# Sheet7.net
KiCad netlist of a schematic drawn in Altium Designer
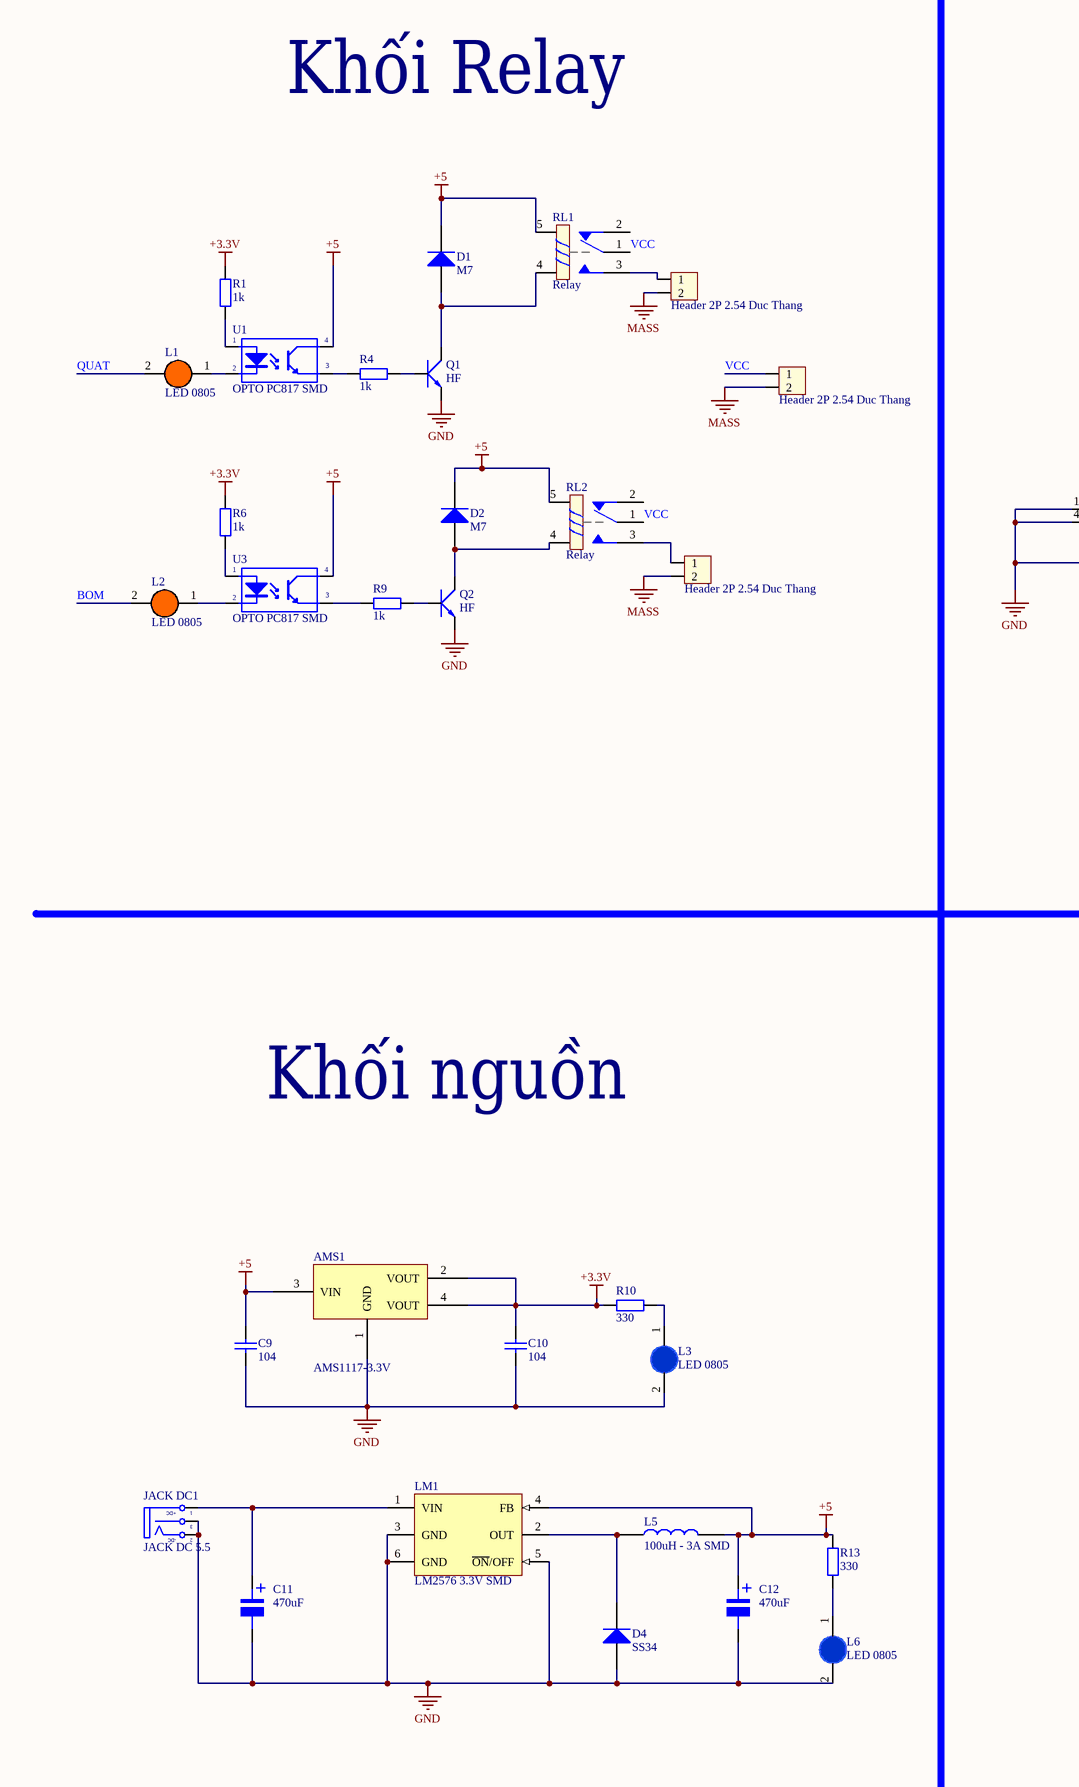
[diagram p0: Sheet7.SchDoc, left]
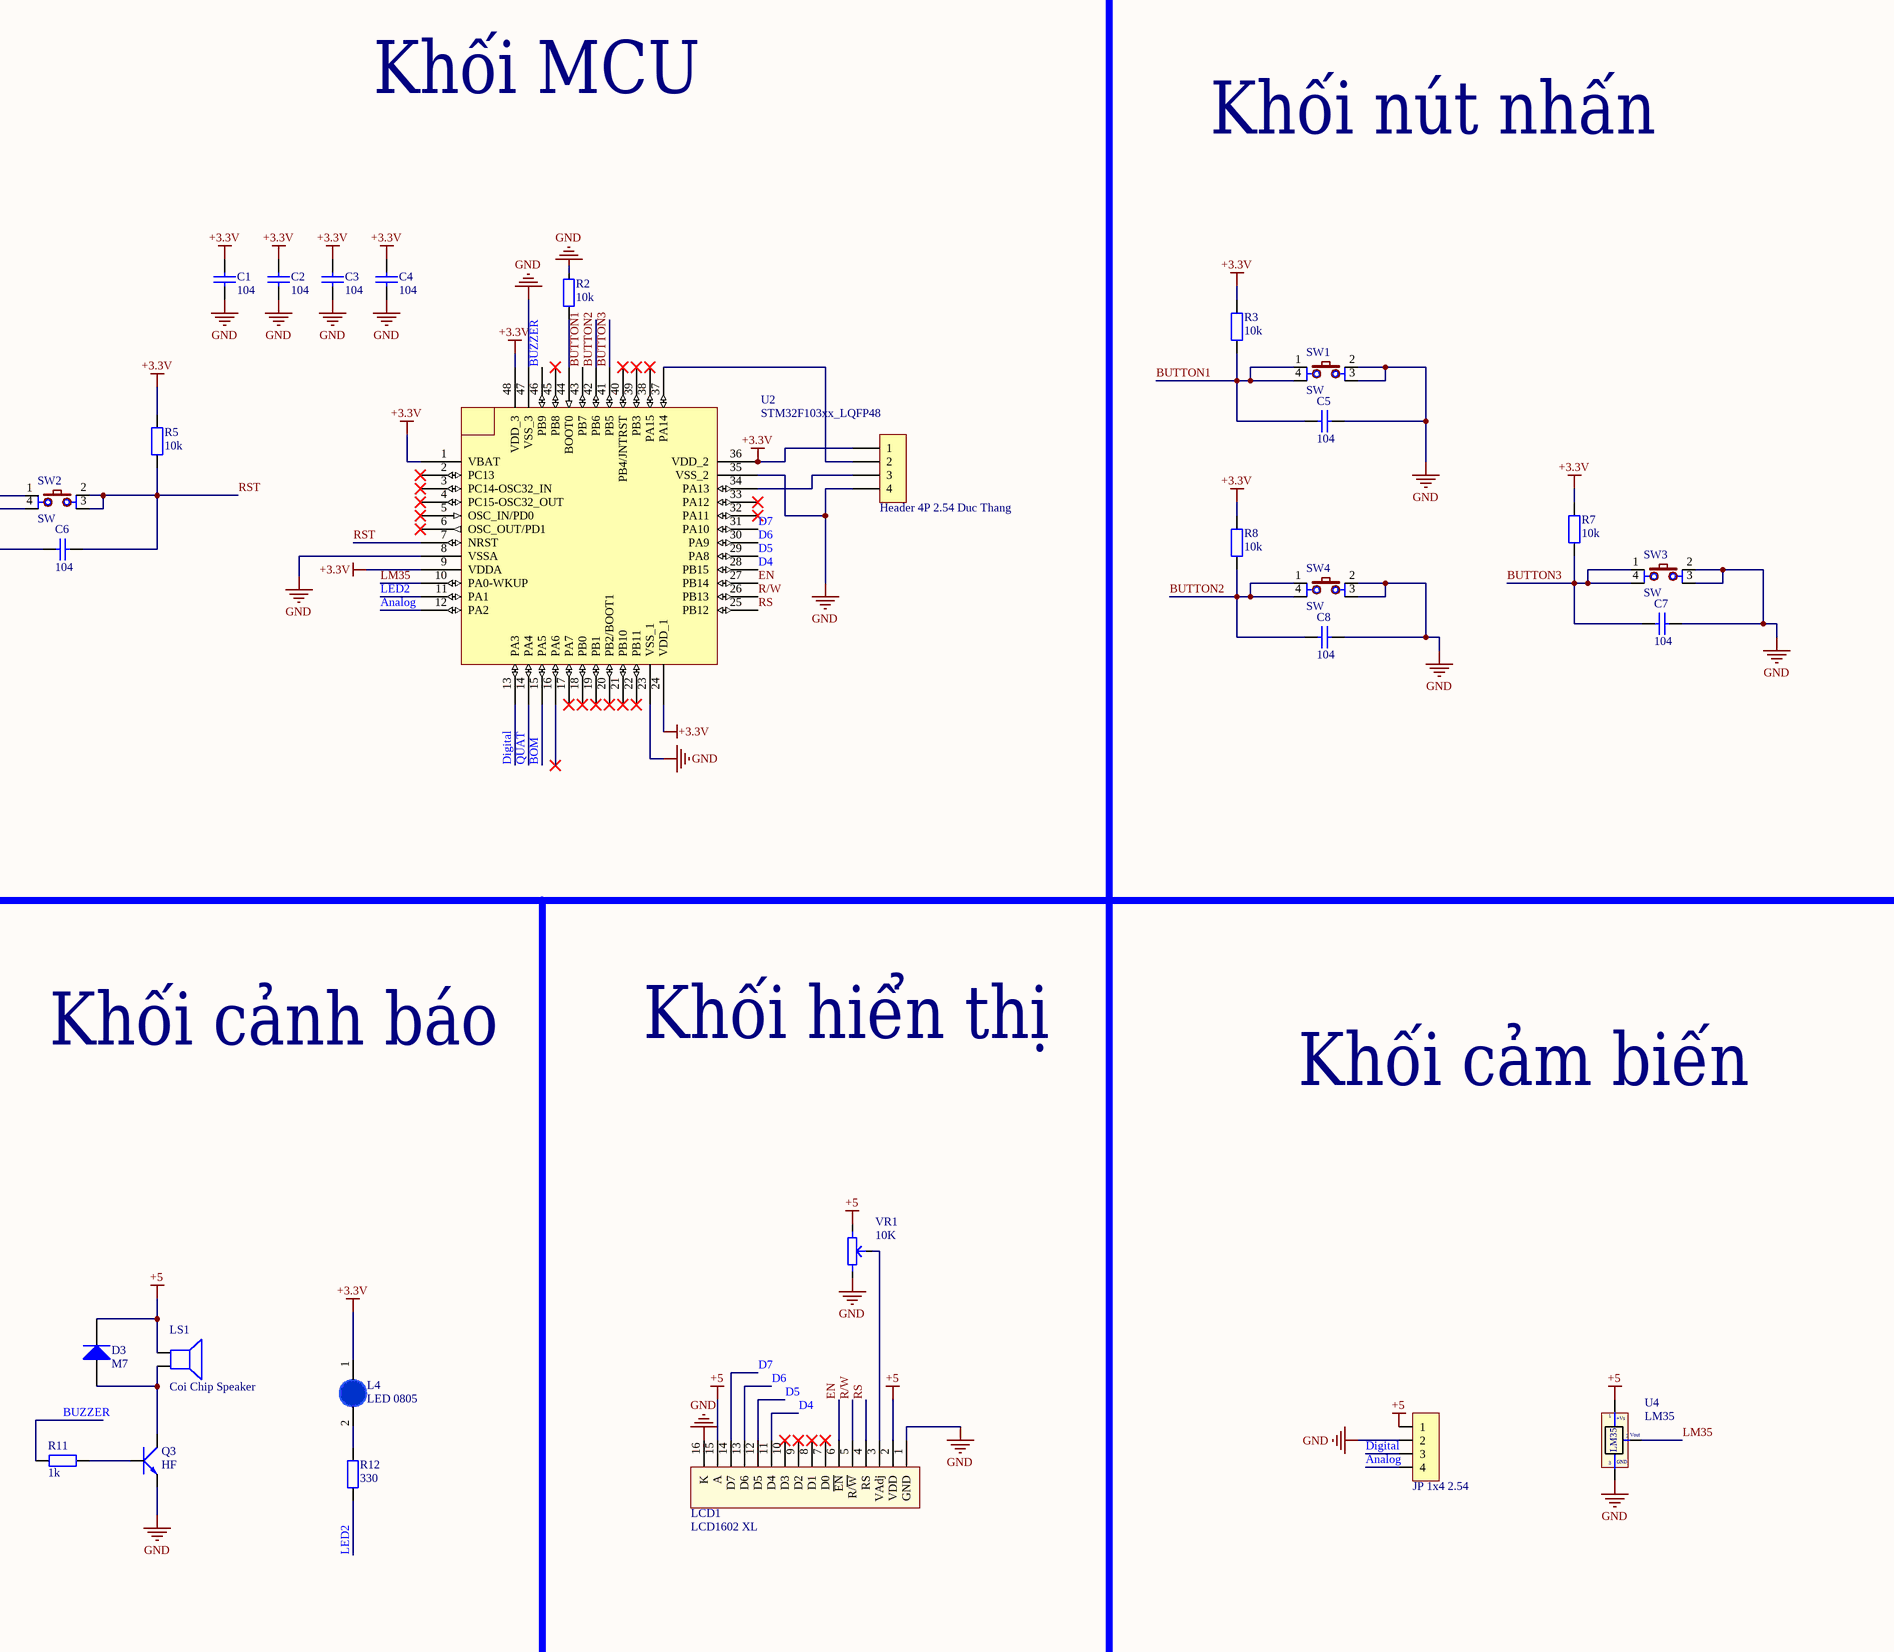
[diagram p1: Sheet7.SchDoc, right]

(export (version "E")
  (design (tool "Eeschema 10.0.6"))
  (components
    (comp (ref "AMS1")
      (value "AMS1117-3.3V")
      (footprint "SOT223")
      (description "Dán")
      (libsource (lib "Altium_Lib_by_KhueNguyenCreator") (part "AMS1117 SMD"))
    )
    (comp (ref "C1")
      (value "104")
      (footprint "tu 0805")
      (description "Dán")
      (libsource (lib "Altium_Lib_by_KhueNguyenCreator") (part "Tu 0805 104 50V 10%"))
    )
    (comp (ref "C2")
      (value "104")
      (footprint "tu 0805")
      (description "Dán")
      (libsource (lib "Altium_Lib_by_KhueNguyenCreator") (part "Tu 0805 104 50V 10%"))
    )
    (comp (ref "C3")
      (value "104")
      (footprint "tu 0805")
      (description "Dán")
      (libsource (lib "Altium_Lib_by_KhueNguyenCreator") (part "Tu 0805 104 50V 10%"))
    )
    (comp (ref "C4")
      (value "104")
      (footprint "tu 0805")
      (description "Dán")
      (libsource (lib "Altium_Lib_by_KhueNguyenCreator") (part "Tu 0805 104 50V 10%"))
    )
    (comp (ref "C5")
      (value "104")
      (footprint "tu 0805")
      (description "Dán")
      (libsource (lib "Altium_Lib_by_KhueNguyenCreator") (part "Tu 0805 104 50V 10%"))
    )
    (comp (ref "C6")
      (value "104")
      (footprint "tu 0805")
      (description "Dán")
      (libsource (lib "Altium_Lib_by_KhueNguyenCreator") (part "Tu 0805 104 50V 10%"))
    )
    (comp (ref "C7")
      (value "104")
      (footprint "tu 0805")
      (description "Dán")
      (libsource (lib "Altium_Lib_by_KhueNguyenCreator") (part "Tu 0805 104 50V 10%"))
    )
    (comp (ref "C8")
      (value "104")
      (footprint "tu 0805")
      (description "Dán")
      (libsource (lib "Altium_Lib_by_KhueNguyenCreator") (part "Tu 0805 104 50V 10%"))
    )
    (comp (ref "C9")
      (value "104")
      (footprint "tu 0805")
      (description "Dán")
      (libsource (lib "Altium_Lib_by_KhueNguyenCreator") (part "Tu 0805 104 50V 10%"))
    )
    (comp (ref "C10")
      (value "104")
      (footprint "tu 0805")
      (description "Dán")
      (libsource (lib "Altium_Lib_by_KhueNguyenCreator") (part "Tu 0805 104 50V 10%"))
    )
    (comp (ref "C11")
      (value "470uF")
      (footprint "tu nhom 8 (f)")
      (description "Dán")
      (libsource (lib "Altium_Lib_by_KhueNguyenCreator") (part "Tu Nhom 470uF 16V"))
    )
    (comp (ref "C12")
      (value "470uF")
      (footprint "tu nhom 8 (f)")
      (description "Dán")
      (libsource (lib "Altium_Lib_by_KhueNguyenCreator") (part "Tu Nhom 470uF 16V"))
    )
    (comp (ref "D1")
      (value "M7")
      (footprint "DIODE SMA")
      (description "Dán")
      (libsource (lib "Altium_Lib_by_KhueNguyenCreator") (part "Diode M7 ( 4007 )"))
    )
    (comp (ref "D2")
      (value "M7")
      (footprint "DIODE SMA")
      (description "Dán")
      (libsource (lib "Altium_Lib_by_KhueNguyenCreator") (part "Diode M7 ( 4007 )"))
    )
    (comp (ref "D3")
      (value "M7")
      (footprint "DIODE SMA")
      (description "Dán")
      (libsource (lib "Altium_Lib_by_KhueNguyenCreator") (part "Diode M7 ( 4007 )"))
    )
    (comp (ref "D4")
      (value "SS34")
      (footprint "DIODE SMA")
      (description "Dán")
      (libsource (lib "Altium_Lib_by_KhueNguyenCreator") (part "Diode SS34 ( 1N5822 )"))
    )
    (comp (ref "H1")
      (value "Header 2P 2.54 Duc Thang")
      (footprint "XH2.54M-2")
      (description "Cắm")
      (libsource (lib "Altium_Lib_by_KhueNguyenCreator") (part "Header 2P 2.54 Duc Thang"))
    )
    (comp (ref "H3")
      (value "Header 4P 2.54 Duc Thang")
      (footprint "XH2.54M-4")
      (description "Cắm")
      (libsource (lib "Altium_Lib_by_KhueNguyenCreator") (part "Header 4P 2.54 Duc Thang"))
    )
    (comp (ref "H7")
      (value "Header 2P 2.54 Duc Thang")
      (footprint "XH2.54M-2")
      (description "Cắm")
      (libsource (lib "Altium_Lib_by_KhueNguyenCreator") (part "Header 2P 2.54 Duc Thang"))
    )
    (comp (ref "H8")
      (value "Header 2P 2.54 Duc Thang")
      (footprint "XH2.54M-2")
      (description "Cắm")
      (libsource (lib "Altium_Lib_by_KhueNguyenCreator") (part "Header 2P 2.54 Duc Thang"))
    )
    (comp (ref "JACK DC1")
      (value "JACK DC 5.5")
      (footprint "JACK DC 5.5")
      (libsource (lib "Altium_Lib_by_KhueNguyenCreator") (part "JACK DC 5.5"))
    )
    (comp (ref "JP1")
      (value "JP 1x4 2.54")
      (footprint "JP 1x4 CT")
      (description "Cắm")
      (libsource (lib "Altium_Lib_by_KhueNguyenCreator") (part "JP 1x4 2.54 Cai Thang"))
    )
    (comp (ref "L1")
      (value "LED 0805")
      (footprint "LED-0805-Orange")
      (description "Dán")
      (libsource (lib "Altium_Lib_by_KhueNguyenCreator") (part "LED 0805 Cam"))
    )
    (comp (ref "L2")
      (value "LED 0805")
      (footprint "LED-0805-Orange")
      (description "Dán")
      (libsource (lib "Altium_Lib_by_KhueNguyenCreator") (part "LED 0805 Cam"))
    )
    (comp (ref "L3")
      (value "LED 0805")
      (footprint "LED-0805-Blue")
      (description "Dán")
      (libsource (lib "Altium_Lib_by_KhueNguyenCreator") (part "LED 0805 Xanh Duong"))
    )
    (comp (ref "L4")
      (value "LED 0805")
      (footprint "LED-0805-Blue")
      (description "Dán")
      (libsource (lib "Altium_Lib_by_KhueNguyenCreator") (part "LED 0805 Xanh Duong"))
    )
    (comp (ref "L5")
      (value "100uH - 3A SMD")
      (footprint "Cuon Cam 12x12x10")
      (description "Dán")
      (libsource (lib "Altium_Lib_by_KhueNguyenCreator") (part "CUON CAM 100uH SMD"))
    )
    (comp (ref "L6")
      (value "LED 0805")
      (footprint "LED-0805-Blue")
      (description "Dán")
      (libsource (lib "Altium_Lib_by_KhueNguyenCreator") (part "LED 0805 Xanh Duong"))
    )
    (comp (ref "LCD1")
      (value "LCD1602 XL")
      (footprint "LCD1602 with Jump")
      (description "LCD 1602 Xanh Lá")
      (libsource (lib "Altium_Lib_by_KhueNguyenCreator") (part "LCD1602 XL"))
    )
    (comp (ref "LM1")
      (value "LM2576 3.3V SMD")
      (footprint "TO263-5")
      (description "Dán")
      (libsource (lib "Altium_Lib_by_KhueNguyenCreator") (part "LM2576 3.3V SMD"))
    )
    (comp (ref "LS1")
      (value "Coi Chip Speaker")
      (footprint "Coi Chip Speacker")
      (description "Còi chip")
      (libsource (lib "Altium_Lib_by_KhueNguyenCreator") (part "Coi Chip Speaker"))
    )
    (comp (ref "Q1")
      (value "HF")
      (footprint "SOT-23")
      (description "SOT-23")
      (libsource (lib "Altium_Lib_by_KhueNguyenCreator") (part "Trans C1815 HF SMD"))
    )
    (comp (ref "Q2")
      (value "HF")
      (footprint "SOT-23")
      (description "SOT-23")
      (libsource (lib "Altium_Lib_by_KhueNguyenCreator") (part "Trans C1815 HF SMD"))
    )
    (comp (ref "Q3")
      (value "HF")
      (footprint "SOT-23")
      (description "SOT-23")
      (libsource (lib "Altium_Lib_by_KhueNguyenCreator") (part "Trans C1815 HF SMD"))
    )
    (comp (ref "R1")
      (value "1k")
      (footprint "tro smd 0805")
      (description "Dán")
      (libsource (lib "Altium_Lib_by_KhueNguyenCreator") (part "Tro 0805 1% 1k"))
    )
    (comp (ref "R2")
      (value "10k")
      (footprint "tro smd 0805")
      (description "Dán")
      (libsource (lib "Altium_Lib_by_KhueNguyenCreator") (part "Tro 0805 1% 18k"))
    )
    (comp (ref "R3")
      (value "10k")
      (footprint "tro smd 0805")
      (description "Dán")
      (libsource (lib "Altium_Lib_by_KhueNguyenCreator") (part "Tro 0805 1% 18k"))
    )
    (comp (ref "R4")
      (value "1k")
      (footprint "tro smd 0805")
      (description "Dán")
      (libsource (lib "Altium_Lib_by_KhueNguyenCreator") (part "Tro 0805 1% 1k"))
    )
    (comp (ref "R5")
      (value "10k")
      (footprint "tro smd 0805")
      (description "Dán")
      (libsource (lib "Altium_Lib_by_KhueNguyenCreator") (part "Tro 0805 1% 18k"))
    )
    (comp (ref "R6")
      (value "1k")
      (footprint "tro smd 0805")
      (description "Dán")
      (libsource (lib "Altium_Lib_by_KhueNguyenCreator") (part "Tro 0805 1% 1k"))
    )
    (comp (ref "R7")
      (value "10k")
      (footprint "tro smd 0805")
      (description "Dán")
      (libsource (lib "Altium_Lib_by_KhueNguyenCreator") (part "Tro 0805 1% 18k"))
    )
    (comp (ref "R8")
      (value "10k")
      (footprint "tro smd 0805")
      (description "Dán")
      (libsource (lib "Altium_Lib_by_KhueNguyenCreator") (part "Tro 0805 1% 18k"))
    )
    (comp (ref "R9")
      (value "1k")
      (footprint "tro smd 0805")
      (description "Dán")
      (libsource (lib "Altium_Lib_by_KhueNguyenCreator") (part "Tro 0805 1% 1k"))
    )
    (comp (ref "R10")
      (value "330")
      (footprint "tro smd 0805")
      (description "Dán")
      (libsource (lib "Altium_Lib_by_KhueNguyenCreator") (part "Tro 0805 1% 18k"))
    )
    (comp (ref "R11")
      (value "1k")
      (footprint "tro smd 0805")
      (description "Dán")
      (libsource (lib "Altium_Lib_by_KhueNguyenCreator") (part "Tro 0805 1% 18k"))
    )
    (comp (ref "R12")
      (value "330")
      (footprint "tro smd 0805")
      (description "Dán")
      (libsource (lib "Altium_Lib_by_KhueNguyenCreator") (part "Tro 0805 1% 18k"))
    )
    (comp (ref "R13")
      (value "330")
      (footprint "tro smd 0805")
      (description "Dán")
      (libsource (lib "Altium_Lib_by_KhueNguyenCreator") (part "Tro 0805 1% 18k"))
    )
    (comp (ref "RL1")
      (value "Relay")
      (footprint "Relay 5 Chan SRD")
      (description "Relay 5 Chan")
      (libsource (lib "Altium_Lib_by_KhueNguyenCreator") (part "Relay 5 Chan SRD"))
    )
    (comp (ref "RL2")
      (value "Relay")
      (footprint "Relay 5 Chan SRD")
      (description "Relay 5 Chan")
      (libsource (lib "Altium_Lib_by_KhueNguyenCreator") (part "Relay 5 Chan SRD"))
    )
    (comp (ref "SW1")
      (value "SW")
      (footprint "SW2-DIP")
      (description "Switch button 4 pin")
      (libsource (lib "LIBRARY1") (part "SW4"))
    )
    (comp (ref "SW2")
      (value "SW")
      (footprint "SW2-DIP")
      (description "Switch button 4 pin")
      (libsource (lib "LIBRARY1") (part "SW4"))
    )
    (comp (ref "SW3")
      (value "SW")
      (footprint "SW2-DIP")
      (description "Switch button 4 pin")
      (libsource (lib "LIBRARY1") (part "SW4"))
    )
    (comp (ref "SW4")
      (value "SW")
      (footprint "SW2-DIP")
      (description "Switch button 4 pin")
      (libsource (lib "LIBRARY1") (part "SW4"))
    )
    (comp (ref "U1")
      (value "OPTO PC817 SMD")
      (footprint "SOP4")
      (description "Single Opto")
      (libsource (lib "Altium_Lib_by_KhueNguyenCreator") (part "OPTO PC817 SMD"))
    )
    (comp (ref "U2")
      (value "STM32F103xx_LQFP48")
      (footprint "STM32_LQPF48")
      (fields (field (name "PUBLISHER") "Altium Limited"))
      (libsource (lib "Altium_Lib_by_KhueNguyenCreator") (part "STM32F103xx_LQFP48"))
    )
    (comp (ref "U3")
      (value "OPTO PC817 SMD")
      (footprint "SOP4")
      (description "Single Opto")
      (libsource (lib "Altium_Lib_by_KhueNguyenCreator") (part "OPTO PC817 SMD"))
    )
    (comp (ref "U4")
      (value "LM35")
      (footprint "QTO-92")
      (description "Teminal")
      (libsource (lib "syhaunguyen") (part "LM35"))
    )
    (comp (ref "VR1")
      (value "10K")
      (footprint "Bien Tro Tam Giac Dung")
      (description "Cắm")
      (libsource (lib "Altium_Lib_by_KhueNguyenCreator") (part "Bien tro tam giac 10K Dung"))
    )
  )
  (nets
    (net (code "1") (name "+3.3V") (class "Default")
      (node (ref "AMS1") (pin "2") (pinfunction "VOUT_2") (pintype "passive"))
      (node (ref "AMS1") (pin "4") (pinfunction "VOUT_4") (pintype "passive"))
      (node (ref "C1") (pin "1") (pinfunction "1_1") (pintype "passive"))
      (node (ref "C10") (pin "1") (pinfunction "1_1") (pintype "passive"))
      (node (ref "C2") (pin "1") (pinfunction "1_1") (pintype "passive"))
      (node (ref "C3") (pin "1") (pinfunction "1_1") (pintype "passive"))
      (node (ref "C4") (pin "1") (pinfunction "1_1") (pintype "passive"))
      (node (ref "H3") (pin "1") (pinfunction "1_1") (pintype "passive"))
      (node (ref "L4") (pin "1") (pinfunction "A_1") (pintype "passive"))
      (node (ref "R1") (pin "2") (pinfunction "2_2") (pintype "passive"))
      (node (ref "R10") (pin "2") (pinfunction "2_2") (pintype "passive"))
      (node (ref "R3") (pin "2") (pinfunction "2_2") (pintype "passive"))
      (node (ref "R5") (pin "2") (pinfunction "2_2") (pintype "passive"))
      (node (ref "R6") (pin "2") (pinfunction "2_2") (pintype "passive"))
      (node (ref "R7") (pin "2") (pinfunction "2_2") (pintype "passive"))
      (node (ref "R8") (pin "2") (pinfunction "2_2") (pintype "passive"))
      (node (ref "U2") (pin "1") (pinfunction "VBAT_1") (pintype "power_in"))
      (node (ref "U2") (pin "24") (pinfunction "VDD_1_24") (pintype "power_in"))
      (node (ref "U2") (pin "36") (pinfunction "VDD_2_36") (pintype "power_in"))
      (node (ref "U2") (pin "48") (pinfunction "VDD_3_48") (pintype "power_in"))
      (node (ref "U2") (pin "9") (pinfunction "VDDA_9") (pintype "power_in"))
    )
    (net (code "2") (name "+5") (class "Default")
      (node (ref "AMS1") (pin "3") (pinfunction "VIN_3") (pintype "passive"))
      (node (ref "C12") (pin "1") (pinfunction "1_1") (pintype "passive"))
      (node (ref "C9") (pin "1") (pinfunction "1_1") (pintype "passive"))
      (node (ref "D1") (pin "2") (pinfunction "K_2") (pintype "passive"))
      (node (ref "D2") (pin "2") (pinfunction "K_2") (pintype "passive"))
      (node (ref "D3") (pin "2") (pinfunction "K_2") (pintype "passive"))
      (node (ref "JP1") (pin "1") (pinfunction "1_1") (pintype "passive"))
      (node (ref "L5") (pin "2") (pinfunction "2_2") (pintype "passive"))
      (node (ref "LCD1") (pin "15") (pinfunction "A_15") (pintype "passive"))
      (node (ref "LCD1") (pin "2") (pinfunction "VDD_2") (pintype "passive"))
      (node (ref "LM1") (pin "4") (pinfunction "FB_4") (pintype "input"))
      (node (ref "LS1") (pin "1") (pinfunction "1_1") (pintype "passive"))
      (node (ref "R13") (pin "2") (pinfunction "2_2") (pintype "passive"))
      (node (ref "RL1") (pin "5") (pinfunction "5_5") (pintype "passive"))
      (node (ref "RL2") (pin "5") (pinfunction "5_5") (pintype "passive"))
      (node (ref "U1") (pin "4") (pinfunction "C_4") (pintype "passive"))
      (node (ref "U3") (pin "4") (pinfunction "C_4") (pintype "passive"))
      (node (ref "U4") (pin "1") (pinfunction "+Vs_1") (pintype "passive"))
      (node (ref "VR1") (pin "1") (pinfunction "1_1") (pintype "passive"))
    )
    (net (code "3") (name "/Analog") (class "Default")
      (node (ref "JP1") (pin "4") (pinfunction "4_4") (pintype "passive"))
      (node (ref "U2") (pin "12") (pinfunction "PA2_12") (pintype "bidirectional"))
    )
    (net (code "4") (name "/BOM") (class "Default")
      (node (ref "L2") (pin "2") (pinfunction "K_2") (pintype "passive"))
      (node (ref "U2") (pin "15") (pinfunction "PA5_15") (pintype "bidirectional"))
    )
    (net (code "5") (name "/BUTTON1") (class "Default")
      (node (ref "C5") (pin "1") (pinfunction "1_1") (pintype "passive"))
      (node (ref "R3") (pin "1") (pinfunction "1_1") (pintype "passive"))
      (node (ref "SW1") (pin "1") (pintype "passive"))
      (node (ref "SW1") (pin "4") (pinfunction "4_4") (pintype "passive"))
      (node (ref "U2") (pin "43") (pinfunction "PB7_43") (pintype "bidirectional"))
    )
    (net (code "6") (name "/BUTTON2") (class "Default")
      (node (ref "C8") (pin "1") (pinfunction "1_1") (pintype "passive"))
      (node (ref "R8") (pin "1") (pinfunction "1_1") (pintype "passive"))
      (node (ref "SW4") (pin "1") (pintype "passive"))
      (node (ref "SW4") (pin "4") (pinfunction "4_4") (pintype "passive"))
      (node (ref "U2") (pin "42") (pinfunction "PB6_42") (pintype "bidirectional"))
    )
    (net (code "7") (name "/BUTTON3") (class "Default")
      (node (ref "C7") (pin "1") (pinfunction "1_1") (pintype "passive"))
      (node (ref "R7") (pin "1") (pinfunction "1_1") (pintype "passive"))
      (node (ref "SW3") (pin "1") (pintype "passive"))
      (node (ref "SW3") (pin "4") (pinfunction "4_4") (pintype "passive"))
      (node (ref "U2") (pin "41") (pinfunction "PB5_41") (pintype "bidirectional"))
    )
    (net (code "8") (name "/BUZZER") (class "Default")
      (node (ref "R11") (pin "1") (pinfunction "1_1") (pintype "passive"))
      (node (ref "U2") (pin "46") (pinfunction "PB9_46") (pintype "bidirectional"))
    )
    (net (code "9") (name "/D4") (class "Default")
      (node (ref "LCD1") (pin "11") (pinfunction "D4_11") (pintype "passive"))
      (node (ref "U2") (pin "28") (pinfunction "PB15_28") (pintype "bidirectional"))
    )
    (net (code "10") (name "/D5") (class "Default")
      (node (ref "LCD1") (pin "12") (pinfunction "D5_12") (pintype "passive"))
      (node (ref "U2") (pin "29") (pinfunction "PA8_29") (pintype "bidirectional"))
    )
    (net (code "11") (name "/D6") (class "Default")
      (node (ref "LCD1") (pin "13") (pinfunction "D6_13") (pintype "passive"))
      (node (ref "U2") (pin "30") (pinfunction "PA9_30") (pintype "bidirectional"))
    )
    (net (code "12") (name "/D7") (class "Default")
      (node (ref "LCD1") (pin "14") (pinfunction "D7_14") (pintype "passive"))
      (node (ref "U2") (pin "31") (pinfunction "PA10_31") (pintype "bidirectional"))
    )
    (net (code "13") (name "/Digital") (class "Default")
      (node (ref "JP1") (pin "3") (pinfunction "3_3") (pintype "passive"))
      (node (ref "U2") (pin "13") (pinfunction "PA3_13") (pintype "bidirectional"))
    )
    (net (code "14") (name "/EN") (class "Default")
      (node (ref "LCD1") (pin "6") (pinfunction "~{EN}_6") (pintype "passive"))
      (node (ref "U2") (pin "27") (pinfunction "PB14_27") (pintype "bidirectional"))
    )
    (net (code "15") (name "/LED2") (class "Default")
      (node (ref "R12") (pin "1") (pinfunction "1_1") (pintype "passive"))
      (node (ref "U2") (pin "11") (pinfunction "PA1_11") (pintype "bidirectional"))
    )
    (net (code "16") (name "/LM35") (class "Default")
      (node (ref "U2") (pin "10") (pinfunction "PA0-WKUP_10") (pintype "bidirectional"))
      (node (ref "U4") (pin "2") (pinfunction "Vout_2") (pintype "passive"))
    )
    (net (code "17") (name "/QUAT") (class "Default")
      (node (ref "L1") (pin "2") (pinfunction "K_2") (pintype "passive"))
      (node (ref "U2") (pin "14") (pinfunction "PA4_14") (pintype "bidirectional"))
    )
    (net (code "18") (name "/RS") (class "Default")
      (node (ref "LCD1") (pin "4") (pinfunction "RS_4") (pintype "passive"))
      (node (ref "U2") (pin "25") (pinfunction "PB12_25") (pintype "bidirectional"))
    )
    (net (code "19") (name "/RST") (class "Default")
      (node (ref "C6") (pin "2") (pinfunction "2_2") (pintype "passive"))
      (node (ref "R5") (pin "1") (pinfunction "1_1") (pintype "passive"))
      (node (ref "SW2") (pin "2") (pinfunction "2_2") (pintype "passive"))
      (node (ref "SW2") (pin "3") (pinfunction "3_3") (pintype "passive"))
      (node (ref "U2") (pin "7") (pinfunction "NRST_7") (pintype "bidirectional"))
    )
    (net (code "20") (name "/R{slash}W") (class "Default")
      (node (ref "LCD1") (pin "5") (pinfunction "R/~{W}_5") (pintype "passive"))
      (node (ref "U2") (pin "26") (pinfunction "PB13_26") (pintype "bidirectional"))
    )
    (net (code "21") (name "/VCC") (class "Default")
      (node (ref "H7") (pin "1") (pinfunction "1_1") (pintype "passive"))
      (node (ref "RL1") (pin "1") (pinfunction "1_1") (pintype "passive"))
      (node (ref "RL2") (pin "1") (pinfunction "1_1") (pintype "passive"))
    )
    (net (code "22") (name "GND") (class "Default")
      (node (ref "AMS1") (pin "1") (pinfunction "GND_1") (pintype "passive"))
      (node (ref "C1") (pin "2") (pinfunction "2_2") (pintype "passive"))
      (node (ref "C10") (pin "2") (pinfunction "2_2") (pintype "passive"))
      (node (ref "C11") (pin "2") (pinfunction "2_2") (pintype "passive"))
      (node (ref "C12") (pin "2") (pinfunction "2_2") (pintype "passive"))
      (node (ref "C2") (pin "2") (pinfunction "2_2") (pintype "passive"))
      (node (ref "C3") (pin "2") (pinfunction "2_2") (pintype "passive"))
      (node (ref "C4") (pin "2") (pinfunction "2_2") (pintype "passive"))
      (node (ref "C5") (pin "2") (pinfunction "2_2") (pintype "passive"))
      (node (ref "C6") (pin "1") (pinfunction "1_1") (pintype "passive"))
      (node (ref "C7") (pin "2") (pinfunction "2_2") (pintype "passive"))
      (node (ref "C8") (pin "2") (pinfunction "2_2") (pintype "passive"))
      (node (ref "C9") (pin "2") (pinfunction "2_2") (pintype "passive"))
      (node (ref "D4") (pin "1") (pinfunction "A_1") (pintype "passive"))
      (node (ref "H3") (pin "4") (pinfunction "4_4") (pintype "passive"))
      (node (ref "JACK DC1") (pin "2") (pinfunction "TN_2") (pintype "passive"))
      (node (ref "JACK DC1") (pin "3") (pinfunction "S_3") (pintype "power_in"))
      (node (ref "JP1") (pin "2") (pinfunction "2_2") (pintype "passive"))
      (node (ref "L3") (pin "2") (pinfunction "K_2") (pintype "passive"))
      (node (ref "L6") (pin "2") (pinfunction "K_2") (pintype "passive"))
      (node (ref "LCD1") (pin "1") (pinfunction "GND_1") (pintype "passive"))
      (node (ref "LCD1") (pin "16") (pinfunction "K_16") (pintype "passive"))
      (node (ref "LM1") (pin "3") (pinfunction "GND_3") (pintype "power_in"))
      (node (ref "LM1") (pin "5") (pinfunction "~{ON}/OFF_5") (pintype "input"))
      (node (ref "LM1") (pin "6") (pinfunction "GND_6") (pintype "passive"))
      (node (ref "Q1") (pin "2") (pinfunction "E_2") (pintype "passive"))
      (node (ref "Q2") (pin "2") (pinfunction "E_2") (pintype "passive"))
      (node (ref "Q3") (pin "2") (pinfunction "E_2") (pintype "passive"))
      (node (ref "R2") (pin "2") (pinfunction "2_2") (pintype "passive"))
      (node (ref "SW1") (pin "2") (pinfunction "2_2") (pintype "passive"))
      (node (ref "SW1") (pin "3") (pinfunction "3_3") (pintype "passive"))
      (node (ref "SW2") (pin "1") (pintype "passive"))
      (node (ref "SW2") (pin "4") (pinfunction "4_4") (pintype "passive"))
      (node (ref "SW3") (pin "2") (pinfunction "2_2") (pintype "passive"))
      (node (ref "SW3") (pin "3") (pinfunction "3_3") (pintype "passive"))
      (node (ref "SW4") (pin "2") (pinfunction "2_2") (pintype "passive"))
      (node (ref "SW4") (pin "3") (pinfunction "3_3") (pintype "passive"))
      (node (ref "U2") (pin "23") (pinfunction "VSS_1_23") (pintype "power_in"))
      (node (ref "U2") (pin "35") (pinfunction "VSS_2_35") (pintype "power_in"))
      (node (ref "U2") (pin "47") (pinfunction "VSS_3_47") (pintype "power_in"))
      (node (ref "U2") (pin "8") (pinfunction "VSSA_8") (pintype "power_in"))
      (node (ref "U4") (pin "3") (pinfunction "-_3") (pintype "passive"))
      (node (ref "VR1") (pin "3") (pinfunction "3_3") (pintype "passive"))
    )
    (net (code "23") (name "MASS") (class "Default")
      (node (ref "H1") (pin "2") (pinfunction "2_2") (pintype "passive"))
      (node (ref "H7") (pin "2") (pinfunction "2_2") (pintype "passive"))
      (node (ref "H8") (pin "2") (pinfunction "2_2") (pintype "passive"))
    )
    (net (code "24") (name "Net-(D1-A)") (class "Default")
      (node (ref "D1") (pin "1") (pinfunction "A_1") (pintype "passive"))
      (node (ref "Q1") (pin "3") (pinfunction "C_3") (pintype "passive"))
      (node (ref "RL1") (pin "4") (pinfunction "4_4") (pintype "passive"))
    )
    (net (code "25") (name "Net-(D2-A)") (class "Default")
      (node (ref "D2") (pin "1") (pinfunction "A_1") (pintype "passive"))
      (node (ref "Q2") (pin "3") (pinfunction "C_3") (pintype "passive"))
      (node (ref "RL2") (pin "4") (pinfunction "4_4") (pintype "passive"))
    )
    (net (code "26") (name "Net-(D3-A)") (class "Default")
      (node (ref "D3") (pin "1") (pinfunction "A_1") (pintype "passive"))
      (node (ref "LS1") (pin "2") (pinfunction "2_2") (pintype "passive"))
      (node (ref "Q3") (pin "3") (pinfunction "C_3") (pintype "passive"))
    )
    (net (code "27") (name "Net-(D4-K)") (class "Default")
      (node (ref "D4") (pin "2") (pinfunction "K_2") (pintype "passive"))
      (node (ref "L5") (pin "1") (pinfunction "1_1") (pintype "passive"))
      (node (ref "LM1") (pin "2") (pinfunction "OUT_2") (pintype "power_in"))
    )
    (net (code "28") (name "Net-(H1-Pad1)") (class "Default")
      (node (ref "H1") (pin "1") (pinfunction "1_1") (pintype "passive"))
      (node (ref "RL1") (pin "3") (pinfunction "3_3") (pintype "passive"))
    )
    (net (code "29") (name "Net-(H8-Pad1)") (class "Default")
      (node (ref "H8") (pin "1") (pinfunction "1_1") (pintype "passive"))
      (node (ref "RL2") (pin "3") (pinfunction "3_3") (pintype "passive"))
    )
    (net (code "30") (name "Net-(JACK DC1-T)") (class "Default")
      (node (ref "C11") (pin "1") (pinfunction "1_1") (pintype "passive"))
      (node (ref "JACK DC1") (pin "1") (pinfunction "T_1") (pintype "passive"))
      (node (ref "LM1") (pin "1") (pinfunction "VIN_1") (pintype "power_in"))
    )
    (net (code "31") (name "Net-(L1-A)") (class "Default")
      (node (ref "L1") (pin "1") (pinfunction "A_1") (pintype "passive"))
      (node (ref "U1") (pin "2") (pinfunction "K_2") (pintype "passive"))
    )
    (net (code "32") (name "Net-(L2-A)") (class "Default")
      (node (ref "L2") (pin "1") (pinfunction "A_1") (pintype "passive"))
      (node (ref "U3") (pin "2") (pinfunction "K_2") (pintype "passive"))
    )
    (net (code "33") (name "Net-(L3-A)") (class "Default")
      (node (ref "L3") (pin "1") (pinfunction "A_1") (pintype "passive"))
      (node (ref "R10") (pin "1") (pinfunction "1_1") (pintype "passive"))
    )
    (net (code "34") (name "Net-(L4-K)") (class "Default")
      (node (ref "L4") (pin "2") (pinfunction "K_2") (pintype "passive"))
      (node (ref "R12") (pin "2") (pinfunction "2_2") (pintype "passive"))
    )
    (net (code "35") (name "Net-(L6-A)") (class "Default")
      (node (ref "L6") (pin "1") (pinfunction "A_1") (pintype "passive"))
      (node (ref "R13") (pin "1") (pinfunction "1_1") (pintype "passive"))
    )
    (net (code "36") (name "Net-(LCD1-VAdj)") (class "Default")
      (node (ref "LCD1") (pin "3") (pinfunction "VAdj_3") (pintype "passive"))
      (node (ref "VR1") (pin "2") (pinfunction "2_2") (pintype "passive"))
    )
    (net (code "37") (name "Net-(Q1-B)") (class "Default")
      (node (ref "Q1") (pin "1") (pinfunction "B_1") (pintype "passive"))
      (node (ref "R4") (pin "1") (pinfunction "1_1") (pintype "passive"))
    )
    (net (code "38") (name "Net-(Q2-B)") (class "Default")
      (node (ref "Q2") (pin "1") (pinfunction "B_1") (pintype "passive"))
      (node (ref "R9") (pin "1") (pinfunction "1_1") (pintype "passive"))
    )
    (net (code "39") (name "Net-(Q3-B)") (class "Default")
      (node (ref "Q3") (pin "1") (pinfunction "B_1") (pintype "passive"))
      (node (ref "R11") (pin "2") (pinfunction "2_2") (pintype "passive"))
    )
    (net (code "40") (name "Net-(U1-A)") (class "Default")
      (node (ref "R1") (pin "1") (pinfunction "1_1") (pintype "passive"))
      (node (ref "U1") (pin "1") (pinfunction "A_1") (pintype "passive"))
    )
    (net (code "41") (name "Net-(U1-E)") (class "Default")
      (node (ref "R4") (pin "2") (pinfunction "2_2") (pintype "passive"))
      (node (ref "U1") (pin "3") (pinfunction "E_3") (pintype "passive"))
    )
    (net (code "42") (name "Net-(U2-BOOT0)") (class "Default")
      (node (ref "R2") (pin "1") (pinfunction "1_1") (pintype "passive"))
      (node (ref "U2") (pin "44") (pinfunction "BOOT0_44") (pintype "input"))
    )
    (net (code "43") (name "Net-(U2-PA13)") (class "Default")
      (node (ref "H3") (pin "3") (pinfunction "3_3") (pintype "passive"))
      (node (ref "U2") (pin "34") (pinfunction "PA13_34") (pintype "bidirectional"))
    )
    (net (code "44") (name "Net-(U2-PA14)") (class "Default")
      (node (ref "H3") (pin "2") (pinfunction "2_2") (pintype "passive"))
      (node (ref "U2") (pin "37") (pinfunction "PA14_37") (pintype "bidirectional"))
    )
    (net (code "45") (name "Net-(U3-A)") (class "Default")
      (node (ref "R6") (pin "1") (pinfunction "1_1") (pintype "passive"))
      (node (ref "U3") (pin "1") (pinfunction "A_1") (pintype "passive"))
    )
    (net (code "46") (name "Net-(U3-E)") (class "Default")
      (node (ref "R9") (pin "2") (pinfunction "2_2") (pintype "passive"))
      (node (ref "U3") (pin "3") (pinfunction "E_3") (pintype "passive"))
    )
    (net (code "47") (name "unconnected-(LCD1-D0-Pad7)") (class "Default")
      (node (ref "LCD1") (pin "7") (pinfunction "D0_7") (pintype "passive+no_connect"))
    )
    (net (code "48") (name "unconnected-(LCD1-D1-Pad8)") (class "Default")
      (node (ref "LCD1") (pin "8") (pinfunction "D1_8") (pintype "passive+no_connect"))
    )
    (net (code "49") (name "unconnected-(LCD1-D2-Pad9)") (class "Default")
      (node (ref "LCD1") (pin "9") (pinfunction "D2_9") (pintype "passive+no_connect"))
    )
    (net (code "50") (name "unconnected-(LCD1-D3-Pad10)") (class "Default")
      (node (ref "LCD1") (pin "10") (pinfunction "D3_10") (pintype "passive+no_connect"))
    )
    (net (code "51") (name "unconnected-(RL1-Pad2)") (class "Default")
      (node (ref "RL1") (pin "2") (pinfunction "2_2") (pintype "passive"))
    )
    (net (code "52") (name "unconnected-(RL2-Pad2)") (class "Default")
      (node (ref "RL2") (pin "2") (pinfunction "2_2") (pintype "passive"))
    )
    (net (code "53") (name "unconnected-(U2-OSC_IN{slash}PD0-Pad5)") (class "Default")
      (node (ref "U2") (pin "5") (pinfunction "OSC_IN/PD0_5") (pintype "input+no_connect"))
    )
    (net (code "54") (name "unconnected-(U2-OSC_OUT{slash}PD1-Pad6)") (class "Default")
      (node (ref "U2") (pin "6") (pinfunction "OSC_OUT/PD1_6") (pintype "output+no_connect"))
    )
    (net (code "55") (name "unconnected-(U2-PA6-Pad16)") (class "Default")
      (node (ref "U2") (pin "16") (pinfunction "PA6_16") (pintype "bidirectional+no_connect"))
    )
    (net (code "56") (name "unconnected-(U2-PA7-Pad17)") (class "Default")
      (node (ref "U2") (pin "17") (pinfunction "PA7_17") (pintype "bidirectional+no_connect"))
    )
    (net (code "57") (name "unconnected-(U2-PA11-Pad32)") (class "Default")
      (node (ref "U2") (pin "32") (pinfunction "PA11_32") (pintype "bidirectional+no_connect"))
    )
    (net (code "58") (name "unconnected-(U2-PA12-Pad33)") (class "Default")
      (node (ref "U2") (pin "33") (pinfunction "PA12_33") (pintype "bidirectional+no_connect"))
    )
    (net (code "59") (name "unconnected-(U2-PA15-Pad38)") (class "Default")
      (node (ref "U2") (pin "38") (pinfunction "PA15_38") (pintype "bidirectional+no_connect"))
    )
    (net (code "60") (name "unconnected-(U2-PB0-Pad18)") (class "Default")
      (node (ref "U2") (pin "18") (pinfunction "PB0_18") (pintype "bidirectional+no_connect"))
    )
    (net (code "61") (name "unconnected-(U2-PB1-Pad19)") (class "Default")
      (node (ref "U2") (pin "19") (pinfunction "PB1_19") (pintype "bidirectional+no_connect"))
    )
    (net (code "62") (name "unconnected-(U2-PB2{slash}BOOT1-Pad20)") (class "Default")
      (node (ref "U2") (pin "20") (pinfunction "PB2/BOOT1_20") (pintype "bidirectional+no_connect"))
    )
    (net (code "63") (name "unconnected-(U2-PB3-Pad39)") (class "Default")
      (node (ref "U2") (pin "39") (pinfunction "PB3_39") (pintype "bidirectional+no_connect"))
    )
    (net (code "64") (name "unconnected-(U2-PB4{slash}JNTRST-Pad40)") (class "Default")
      (node (ref "U2") (pin "40") (pinfunction "PB4/JNTRST_40") (pintype "bidirectional+no_connect"))
    )
    (net (code "65") (name "unconnected-(U2-PB8-Pad45)") (class "Default")
      (node (ref "U2") (pin "45") (pinfunction "PB8_45") (pintype "bidirectional+no_connect"))
    )
    (net (code "66") (name "unconnected-(U2-PB10-Pad21)") (class "Default")
      (node (ref "U2") (pin "21") (pinfunction "PB10_21") (pintype "bidirectional+no_connect"))
    )
    (net (code "67") (name "unconnected-(U2-PB11-Pad22)") (class "Default")
      (node (ref "U2") (pin "22") (pinfunction "PB11_22") (pintype "bidirectional+no_connect"))
    )
    (net (code "68") (name "unconnected-(U2-PC13-Pad2)") (class "Default")
      (node (ref "U2") (pin "2") (pinfunction "PC13_2") (pintype "bidirectional+no_connect"))
    )
    (net (code "69") (name "unconnected-(U2-PC14-OSC32_IN-Pad3)") (class "Default")
      (node (ref "U2") (pin "3") (pinfunction "PC14-OSC32_IN_3") (pintype "bidirectional+no_connect"))
    )
    (net (code "70") (name "unconnected-(U2-PC15-OSC32_OUT-Pad4)") (class "Default")
      (node (ref "U2") (pin "4") (pinfunction "PC15-OSC32_OUT_4") (pintype "bidirectional+no_connect"))
    )
  )
)
